# V04.net
KiCad netlist of a schematic drawn in Altium Designer
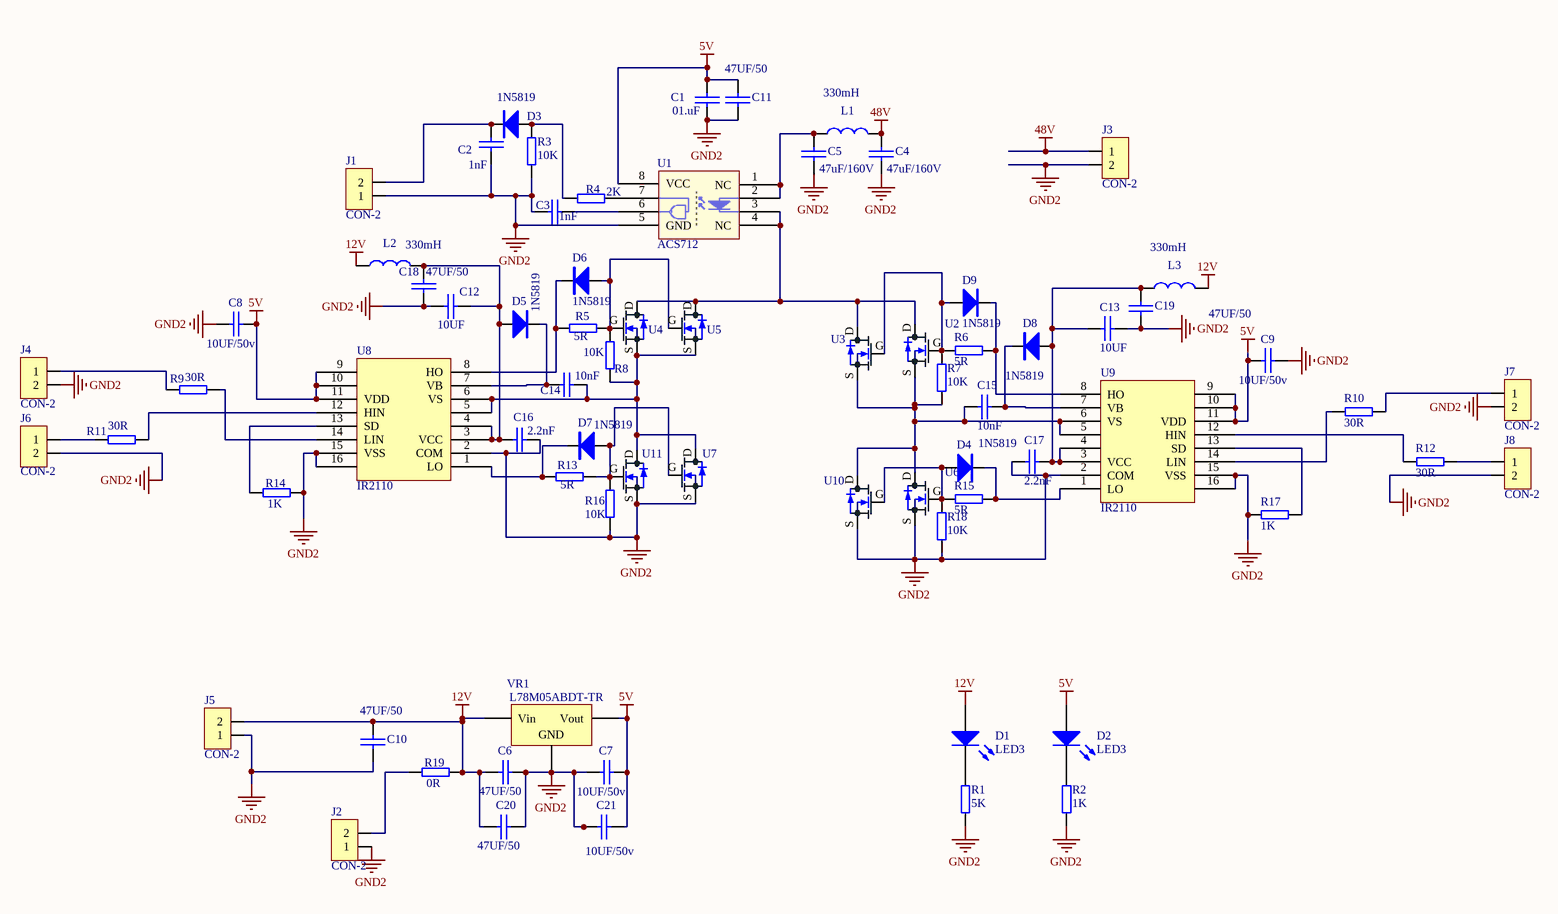
[diagram p0: 发送端V04.SchDoc]

(export (version "E")
  (design (tool "Eeschema 10.0.6"))
  (components
    (comp (ref "C1") (value "01.uF") (footprint "1206_C") (libsource (lib "WegeV1") (part "CAP")))
    (comp (ref "C2") (value "1nF") (footprint "1206_C") (libsource (lib "WegeV1") (part "CAP")))
    (comp (ref "C3") (value "1nF") (footprint "1206_C") (libsource (lib "WegeV1") (part "CAP")))
    (comp (ref "C4") (value "47uF/160V") (footprint "C3618") (libsource (lib "WegeV1") (part "CAP")))
    (comp (ref "C5") (value "47uF/160V") (footprint "C3618") (libsource (lib "WegeV1") (part "CAP")))
    (comp (ref "C6") (value "47UF/50") (footprint "1206_C") (libsource (lib "WegeV1") (part "CAP")))
    (comp (ref "C7") (value "10UF/50v") (footprint "1206_C") (libsource (lib "WegeV1") (part "CAP")))
    (comp (ref "C8") (value "10UF/50v") (footprint "1206_C") (libsource (lib "WegeV1") (part "CAP")))
    (comp (ref "C9") (value "10UF/50v") (footprint "1206_C") (libsource (lib "WegeV1") (part "CAP")))
    (comp (ref "C10") (value "47UF/50") (footprint "C1020") (libsource (lib "WegeV1") (part "CAP")))
    (comp (ref "C11") (value "47UF/50") (footprint "C1020") (libsource (lib "WegeV1") (part "CAP")))
    (comp (ref "C12") (value "10UF") (footprint "1206_C") (libsource (lib "WegeV1") (part "CAP")))
    (comp (ref "C13") (value "10UF") (footprint "1206_C") (libsource (lib "WegeV1") (part "CAP")))
    (comp (ref "C14") (value "10nF") (footprint "1206_C") (libsource (lib "WegeV1") (part "CAP")))
    (comp (ref "C15") (value "10nF") (footprint "1206_C") (libsource (lib "WegeV1") (part "CAP")))
    (comp (ref "C16") (value "2.2nF") (footprint "1206_C") (libsource (lib "WegeV1") (part "CAP")))
    (comp (ref "C17") (value "2.2nF") (footprint "1206_C") (libsource (lib "WegeV1") (part "CAP")))
    (comp (ref "C18") (value "47UF/50") (footprint "C1020") (libsource (lib "WegeV1") (part "CAP")))
    (comp (ref "C19") (value "47UF/50") (footprint "C1020") (libsource (lib "WegeV1") (part "CAP")))
    (comp (ref "C20") (value "47UF/50") (footprint "1206_C") (libsource (lib "WegeV1") (part "CAP")))
    (comp (ref "C21") (value "10UF/50v") (footprint "1206_C") (libsource (lib "WegeV1") (part "CAP")))
    (comp (ref "D1")
      (value "LED3")
      (footprint "1206_R")
      (description "Typical BLUE SiC LED")
      (fields (field (name "PUBLISHER") "Altium Limited"))
      (libsource (lib "Miscellaneous Devices") (part "LED3"))
    )
    (comp (ref "D2")
      (value "LED3")
      (footprint "1206_R")
      (description "Typical BLUE SiC LED")
      (fields (field (name "PUBLISHER") "Altium Limited"))
      (libsource (lib "Miscellaneous Devices") (part "LED3"))
    )
    (comp (ref "D3")
      (value "1N5819")
      (footprint "1206_R")
      (description "1N4148WS IN4148 0805 SOD323 丝印T4 贴片开关二极管")
      (libsource (lib "WegeV1") (part "1N4148"))
    )
    (comp (ref "D4")
      (value "1N5819")
      (footprint "1206_R")
      (description "1N4148WS IN4148 0805 SOD323 丝印T4 贴片开关二极管")
      (libsource (lib "WegeV1") (part "1N4148"))
    )
    (comp (ref "D5")
      (value "1N5819")
      (footprint "1206_R")
      (description "1N4148WS IN4148 0805 SOD323 丝印T4 贴片开关二极管")
      (libsource (lib "WegeV1") (part "1N4148"))
    )
    (comp (ref "D6")
      (value "1N5819")
      (footprint "1206_R")
      (description "1N4148WS IN4148 0805 SOD323 丝印T4 贴片开关二极管")
      (libsource (lib "WegeV1") (part "1N4148"))
    )
    (comp (ref "D7")
      (value "1N5819")
      (footprint "1206_R")
      (description "1N4148WS IN4148 0805 SOD323 丝印T4 贴片开关二极管")
      (libsource (lib "WegeV1") (part "1N4148"))
    )
    (comp (ref "D8")
      (value "1N5819")
      (footprint "1206_R")
      (description "1N4148WS IN4148 0805 SOD323 丝印T4 贴片开关二极管")
      (libsource (lib "WegeV1") (part "1N4148"))
    )
    (comp (ref "D9")
      (value "1N5819")
      (footprint "1206_R")
      (description "1N4148WS IN4148 0805 SOD323 丝印T4 贴片开关二极管")
      (libsource (lib "WegeV1") (part "1N4148"))
    )
    (comp (ref "J1") (value "CON-2") (footprint "HDR1X2") (libsource (lib "") (part "CON-2_1")))
    (comp (ref "J2") (value "CON-2") (footprint "HDR1X2") (libsource (lib "") (part "CON-2_1")))
    (comp (ref "J3") (value "CON-2") (footprint "F396P2-1") (libsource (lib "") (part "CON-2_2")))
    (comp (ref "J4") (value "CON-2") (footprint "GPSPIN") (libsource (lib "WegeV1") (part "CON-2")))
    (comp (ref "J5") (value "CON-2") (footprint "F396P2-1") (libsource (lib "") (part "CON-2_1")))
    (comp (ref "J6") (value "CON-2") (footprint "GPSPIN") (libsource (lib "WegeV1") (part "CON-2")))
    (comp (ref "J7") (value "CON-2") (footprint "GPSPIN") (libsource (lib "") (part "CON-2_2")))
    (comp (ref "J8") (value "CON-2") (footprint "GPSPIN") (libsource (lib "") (part "CON-2_2")))
    (comp (ref "L1")
      (value "330mH")
      (footprint "H3.3")
      (description "CD75--2.2mH 222M 贴片功率电感绕线功率电感 7*7.8*5mm")
      (libsource (lib "WegeV1") (part "INL"))
    )
    (comp (ref "L2")
      (value "330mH")
      (footprint "H3.3")
      (description "CD75--2.2mH 222M 贴片功率电感绕线功率电感 7*7.8*5mm")
      (libsource (lib "WegeV1") (part "INL"))
    )
    (comp (ref "L3")
      (value "330mH")
      (footprint "H3.3")
      (description "CD75--2.2mH 222M 贴片功率电感绕线功率电感 7*7.8*5mm")
      (libsource (lib "WegeV1") (part "INL"))
    )
    (comp (ref "R1") (value "5K") (footprint "1206_R") (libsource (lib "WegeV1") (part "RES")))
    (comp (ref "R2") (value "1K") (footprint "1206_R") (libsource (lib "WegeV1") (part "RES")))
    (comp (ref "R3") (value "10K") (footprint "1206_R") (libsource (lib "WegeV1") (part "RES")))
    (comp (ref "R4") (value "2K") (footprint "1206_R") (libsource (lib "WegeV1") (part "RES")))
    (comp (ref "R5") (value "5R") (footprint "1206_R") (libsource (lib "WegeV1") (part "RES")))
    (comp (ref "R6") (value "5R") (footprint "1206_R") (libsource (lib "WegeV1") (part "RES")))
    (comp (ref "R7") (value "10K") (footprint "1206_R") (libsource (lib "WegeV1") (part "RES")))
    (comp (ref "R8") (value "10K") (footprint "1206_R") (libsource (lib "WegeV1") (part "RES")))
    (comp (ref "R9") (value "30R") (footprint "1206_R") (libsource (lib "WegeV1") (part "RES")))
    (comp (ref "R10") (value "30R") (footprint "1206_R") (libsource (lib "WegeV1") (part "RES")))
    (comp (ref "R11") (value "30R") (footprint "1206_R") (libsource (lib "WegeV1") (part "RES")))
    (comp (ref "R12") (value "30R") (footprint "1206_R") (libsource (lib "WegeV1") (part "RES")))
    (comp (ref "R13") (value "5R") (footprint "1206_R") (libsource (lib "WegeV1") (part "RES")))
    (comp (ref "R14") (value "1K") (footprint "1206_R") (libsource (lib "WegeV1") (part "RES")))
    (comp (ref "R15") (value "5R") (footprint "1206_R") (libsource (lib "WegeV1") (part "RES")))
    (comp (ref "R16") (value "10K") (footprint "1206_R") (libsource (lib "WegeV1") (part "RES")))
    (comp (ref "R17") (value "1K") (footprint "1206_R") (libsource (lib "WegeV1") (part "RES")))
    (comp (ref "R18") (value "10K") (footprint "1206_R") (libsource (lib "WegeV1") (part "RES")))
    (comp (ref "R19") (value "0R") (footprint "1206_R") (libsource (lib "WegeV1") (part "RES")))
    (comp (ref "U1")
      (value "ACS712")
      (footprint "SOIC-8_150mil")
      (description "贴片光耦")
      (libsource (lib "Miscellaneous Devices LC") (part "6N137S(TA)_[C16496]"))
    )
    (comp (ref "U2") (value "IKW50N60H3") (footprint "TO-220") (libsource (lib "WegeV1") (part "NMOS")))
    (comp (ref "U3") (value "IKW50N60H3") (footprint "DDPak") (libsource (lib "WegeV1") (part "NMOS")))
    (comp (ref "U4") (value "IKW50N60H3") (footprint "TO-220") (libsource (lib "WegeV1") (part "NMOS")))
    (comp (ref "U5") (value "IKW50N60H3") (footprint "DDPak") (libsource (lib "WegeV1") (part "NMOS")))
    (comp (ref "U6") (value "IRFP4868") (footprint "TO-220") (libsource (lib "WegeV1") (part "NMOS")))
    (comp (ref "U7") (value "IRFP4868") (footprint "DDPak") (libsource (lib "WegeV1") (part "NMOS")))
    (comp (ref "U8")
      (value "IR2110")
      (footprint "SOIC-16_300mil")
      (libsource (lib "IC_temp") (part "IR2110"))
    )
    (comp (ref "U9") (value "IR2110") (footprint "SOIC-16_300mil") (libsource (lib "") (part "IR2110_1")))
    (comp (ref "U10") (value "IRFP4868") (footprint "DDPak") (libsource (lib "WegeV1") (part "NMOS")))
    (comp (ref "U11") (value "IRFP4868") (footprint "TO-220") (libsource (lib "WegeV1") (part "NMOS")))
    (comp (ref "VR1")
      (value "L78M05ABDT-TR")
      (footprint "TO-220")
      (description "低压差线性稳压(LDO)")
      (libsource (lib "Miscellaneous Devices LC") (part "TO-252-2 L78M05ABDT-TR"))
    )
  )
  (nets
    (net (code "1") (name "5V") (class "Default")
      (node (ref "C1") (pin "1") (pinfunction "1_1") (pintype "passive"))
      (node (ref "C11") (pin "1") (pinfunction "1_1") (pintype "passive"))
      (node (ref "C21") (pin "1") (pinfunction "1_1") (pintype "passive"))
      (node (ref "C7") (pin "1") (pinfunction "1_1") (pintype "passive"))
      (node (ref "C8") (pin "1") (pinfunction "1_1") (pintype "passive"))
      (node (ref "C9") (pin "2") (pinfunction "2_2") (pintype "passive"))
      (node (ref "D2") (pin "1") (pinfunction "A_1") (pintype "passive"))
      (node (ref "U1") (pin "8") (pinfunction "VCC_8") (pintype "passive"))
      (node (ref "U8") (pin "10") (pintype "passive"))
      (node (ref "U8") (pin "11") (pinfunction "VDD_11") (pintype "passive"))
      (node (ref "U8") (pin "9") (pintype "passive"))
      (node (ref "U9") (pin "10") (pintype "passive"))
      (node (ref "U9") (pin "11") (pinfunction "VDD_11") (pintype "passive"))
      (node (ref "U9") (pin "9") (pintype "passive"))
      (node (ref "VR1") (pin "S") (pinfunction "Vout_S") (pintype "passive"))
    )
    (net (code "2") (name "12V") (class "Default")
      (node (ref "C10") (pin "1") (pinfunction "1_1") (pintype "passive"))
      (node (ref "C20") (pin "2") (pinfunction "2_2") (pintype "passive"))
      (node (ref "C6") (pin "2") (pinfunction "2_2") (pintype "passive"))
      (node (ref "D1") (pin "1") (pinfunction "A_1") (pintype "passive"))
      (node (ref "J5") (pin "2") (pinfunction "2_2") (pintype "passive"))
      (node (ref "L2") (pin "2") (pinfunction "2_2") (pintype "passive"))
      (node (ref "L3") (pin "1") (pinfunction "1_1") (pintype "passive"))
      (node (ref "R19") (pin "2") (pinfunction "2_2") (pintype "passive"))
      (node (ref "VR1") (pin "G") (pinfunction "Vin_G") (pintype "passive"))
    )
    (net (code "3") (name "48V") (class "Default")
      (node (ref "C4") (pin "1") (pinfunction "1_1") (pintype "passive"))
      (node (ref "J3") (pin "1") (pinfunction "1_1") (pintype "passive"))
      (node (ref "L1") (pin "1") (pinfunction "1_1") (pintype "passive"))
    )
    (net (code "4") (name "GND2") (class "Default")
      (node (ref "C1") (pin "2") (pinfunction "2_2") (pintype "passive"))
      (node (ref "C10") (pin "2") (pinfunction "2_2") (pintype "passive"))
      (node (ref "C11") (pin "2") (pinfunction "2_2") (pintype "passive"))
      (node (ref "C12") (pin "2") (pinfunction "2_2") (pintype "passive"))
      (node (ref "C13") (pin "2") (pinfunction "2_2") (pintype "passive"))
      (node (ref "C16") (pin "1") (pinfunction "1_1") (pintype "passive"))
      (node (ref "C17") (pin "1") (pinfunction "1_1") (pintype "passive"))
      (node (ref "C18") (pin "2") (pinfunction "2_2") (pintype "passive"))
      (node (ref "C19") (pin "2") (pinfunction "2_2") (pintype "passive"))
      (node (ref "C2") (pin "2") (pinfunction "2_2") (pintype "passive"))
      (node (ref "C20") (pin "1") (pinfunction "1_1") (pintype "passive"))
      (node (ref "C21") (pin "2") (pinfunction "2_2") (pintype "passive"))
      (node (ref "C3") (pin "2") (pinfunction "2_2") (pintype "passive"))
      (node (ref "C4") (pin "2") (pinfunction "2_2") (pintype "passive"))
      (node (ref "C5") (pin "2") (pinfunction "2_2") (pintype "passive"))
      (node (ref "C6") (pin "1") (pinfunction "1_1") (pintype "passive"))
      (node (ref "C7") (pin "2") (pinfunction "2_2") (pintype "passive"))
      (node (ref "C8") (pin "2") (pinfunction "2_2") (pintype "passive"))
      (node (ref "C9") (pin "1") (pinfunction "1_1") (pintype "passive"))
      (node (ref "J1") (pin "1") (pinfunction "1_1") (pintype "passive"))
      (node (ref "J2") (pin "1") (pinfunction "1_1") (pintype "passive"))
      (node (ref "J3") (pin "2") (pinfunction "2_2") (pintype "passive"))
      (node (ref "J4") (pin "2") (pinfunction "2_2") (pintype "passive"))
      (node (ref "J5") (pin "1") (pinfunction "1_1") (pintype "passive"))
      (node (ref "J6") (pin "2") (pinfunction "2_2") (pintype "passive"))
      (node (ref "J7") (pin "2") (pinfunction "2_2") (pintype "passive"))
      (node (ref "J8") (pin "2") (pinfunction "2_2") (pintype "passive"))
      (node (ref "R1") (pin "1") (pinfunction "1_1") (pintype "passive"))
      (node (ref "R14") (pin "2") (pinfunction "2_2") (pintype "passive"))
      (node (ref "R16") (pin "1") (pinfunction "1_1") (pintype "passive"))
      (node (ref "R17") (pin "2") (pinfunction "2_2") (pintype "passive"))
      (node (ref "R18") (pin "1") (pinfunction "1_1") (pintype "passive"))
      (node (ref "R2") (pin "1") (pinfunction "1_1") (pintype "passive"))
      (node (ref "R3") (pin "2") (pinfunction "2_2") (pintype "passive"))
      (node (ref "U1") (pin "5") (pinfunction "GND_5") (pintype "passive"))
      (node (ref "U10") (pin "S") (pinfunction "S_S") (pintype "passive"))
      (node (ref "U11") (pin "S") (pinfunction "S_S") (pintype "passive"))
      (node (ref "U6") (pin "S") (pinfunction "S_S") (pintype "passive"))
      (node (ref "U7") (pin "S") (pinfunction "S_S") (pintype "passive"))
      (node (ref "U8") (pin "15") (pinfunction "VSS_15") (pintype "passive"))
      (node (ref "U8") (pin "16") (pintype "passive"))
      (node (ref "U8") (pin "2") (pinfunction "COM_2") (pintype "passive"))
      (node (ref "U9") (pin "15") (pinfunction "VSS_15") (pintype "passive"))
      (node (ref "U9") (pin "16") (pintype "passive"))
      (node (ref "U9") (pin "2") (pinfunction "COM_2") (pintype "passive"))
      (node (ref "VR1") (pin "D") (pinfunction "GND_D") (pintype "passive"))
    )
    (net (code "5") (name "Net-(D1-K)") (class "Default")
      (node (ref "D1") (pin "2") (pinfunction "K_2") (pintype "passive"))
      (node (ref "R1") (pin "2") (pinfunction "2_2") (pintype "passive"))
    )
    (net (code "6") (name "Net-(D2-K)") (class "Default")
      (node (ref "D2") (pin "2") (pinfunction "K_2") (pintype "passive"))
      (node (ref "R2") (pin "2") (pinfunction "2_2") (pintype "passive"))
    )
    (net (code "7") (name "Net-(D3-A)") (class "Default")
      (node (ref "D3") (pin "1") (pinfunction "A_1") (pintype "passive"))
      (node (ref "R3") (pin "1") (pinfunction "1_1") (pintype "passive"))
      (node (ref "R4") (pin "2") (pinfunction "2_2") (pintype "passive"))
    )
    (net (code "8") (name "Net-(D3-K)") (class "Default")
      (node (ref "C2") (pin "1") (pinfunction "1_1") (pintype "passive"))
      (node (ref "D3") (pin "2") (pinfunction "K_2") (pintype "passive"))
      (node (ref "J1") (pin "2") (pinfunction "2_2") (pintype "passive"))
    )
    (net (code "9") (name "Net-(D4-A)") (class "Default")
      (node (ref "D4") (pin "1") (pinfunction "A_1") (pintype "passive"))
      (node (ref "R15") (pin "2") (pinfunction "2_2") (pintype "passive"))
      (node (ref "R18") (pin "2") (pinfunction "2_2") (pintype "passive"))
      (node (ref "U10") (pin "G") (pinfunction "G_G") (pintype "passive"))
      (node (ref "U6") (pin "G") (pinfunction "G_G") (pintype "passive"))
    )
    (net (code "10") (name "Net-(D4-K)") (class "Default")
      (node (ref "D4") (pin "2") (pinfunction "K_2") (pintype "passive"))
      (node (ref "R15") (pin "1") (pinfunction "1_1") (pintype "passive"))
      (node (ref "U9") (pin "1") (pinfunction "LO_1") (pintype "passive"))
    )
    (net (code "11") (name "Net-(D5-A)") (class "Default")
      (node (ref "C12") (pin "1") (pinfunction "1_1") (pintype "passive"))
      (node (ref "C16") (pin "2") (pinfunction "2_2") (pintype "passive"))
      (node (ref "C18") (pin "1") (pinfunction "1_1") (pintype "passive"))
      (node (ref "D5") (pin "1") (pinfunction "A_1") (pintype "passive"))
      (node (ref "L2") (pin "1") (pinfunction "1_1") (pintype "passive"))
      (node (ref "U8") (pin "3") (pinfunction "VCC_3") (pintype "passive"))
      (node (ref "U8") (pin "4") (pintype "passive"))
    )
    (net (code "12") (name "Net-(D5-K)") (class "Default")
      (node (ref "C14") (pin "2") (pinfunction "2_2") (pintype "passive"))
      (node (ref "D5") (pin "2") (pinfunction "K_2") (pintype "passive"))
      (node (ref "U8") (pin "7") (pinfunction "VB_7") (pintype "passive"))
    )
    (net (code "13") (name "Net-(D6-A)") (class "Default")
      (node (ref "D6") (pin "1") (pinfunction "A_1") (pintype "passive"))
      (node (ref "R5") (pin "2") (pinfunction "2_2") (pintype "passive"))
      (node (ref "R8") (pin "2") (pinfunction "2_2") (pintype "passive"))
      (node (ref "U4") (pin "G") (pinfunction "G_G") (pintype "passive"))
      (node (ref "U5") (pin "G") (pinfunction "G_G") (pintype "passive"))
    )
    (net (code "14") (name "Net-(D6-K)") (class "Default")
      (node (ref "D6") (pin "2") (pinfunction "K_2") (pintype "passive"))
      (node (ref "R5") (pin "1") (pinfunction "1_1") (pintype "passive"))
      (node (ref "U8") (pin "8") (pinfunction "HO_8") (pintype "passive"))
    )
    (net (code "15") (name "Net-(D7-A)") (class "Default")
      (node (ref "D7") (pin "1") (pinfunction "A_1") (pintype "passive"))
      (node (ref "R13") (pin "2") (pinfunction "2_2") (pintype "passive"))
      (node (ref "R16") (pin "2") (pinfunction "2_2") (pintype "passive"))
      (node (ref "U11") (pin "G") (pinfunction "G_G") (pintype "passive"))
      (node (ref "U7") (pin "G") (pinfunction "G_G") (pintype "passive"))
    )
    (net (code "16") (name "Net-(D7-K)") (class "Default")
      (node (ref "D7") (pin "2") (pinfunction "K_2") (pintype "passive"))
      (node (ref "R13") (pin "1") (pinfunction "1_1") (pintype "passive"))
      (node (ref "U8") (pin "1") (pinfunction "LO_1") (pintype "passive"))
    )
    (net (code "17") (name "Net-(D8-A)") (class "Default")
      (node (ref "C13") (pin "1") (pinfunction "1_1") (pintype "passive"))
      (node (ref "C17") (pin "2") (pinfunction "2_2") (pintype "passive"))
      (node (ref "C19") (pin "1") (pinfunction "1_1") (pintype "passive"))
      (node (ref "D8") (pin "1") (pinfunction "A_1") (pintype "passive"))
      (node (ref "L3") (pin "2") (pinfunction "2_2") (pintype "passive"))
      (node (ref "U9") (pin "3") (pinfunction "VCC_3") (pintype "passive"))
      (node (ref "U9") (pin "4") (pintype "passive"))
    )
    (net (code "18") (name "Net-(D8-K)") (class "Default")
      (node (ref "C15") (pin "2") (pinfunction "2_2") (pintype "passive"))
      (node (ref "D8") (pin "2") (pinfunction "K_2") (pintype "passive"))
      (node (ref "U9") (pin "7") (pinfunction "VB_7") (pintype "passive"))
    )
    (net (code "19") (name "Net-(D9-A)") (class "Default")
      (node (ref "D9") (pin "1") (pinfunction "A_1") (pintype "passive"))
      (node (ref "R6") (pin "2") (pinfunction "2_2") (pintype "passive"))
      (node (ref "R7") (pin "2") (pinfunction "2_2") (pintype "passive"))
      (node (ref "U2") (pin "G") (pinfunction "G_G") (pintype "passive"))
      (node (ref "U3") (pin "G") (pinfunction "G_G") (pintype "passive"))
    )
    (net (code "20") (name "Net-(D9-K)") (class "Default")
      (node (ref "D9") (pin "2") (pinfunction "K_2") (pintype "passive"))
      (node (ref "R6") (pin "1") (pinfunction "1_1") (pintype "passive"))
      (node (ref "U9") (pin "8") (pinfunction "HO_8") (pintype "passive"))
    )
    (net (code "21") (name "Net-(J2-Pad2)") (class "Default")
      (node (ref "J2") (pin "2") (pinfunction "2_2") (pintype "passive"))
      (node (ref "R19") (pin "1") (pinfunction "1_1") (pintype "passive"))
    )
    (net (code "22") (name "Net-(J4-Pad1)") (class "Default")
      (node (ref "J4") (pin "1") (pinfunction "1_1") (pintype "passive"))
      (node (ref "R9") (pin "1") (pinfunction "1_1") (pintype "passive"))
    )
    (net (code "23") (name "Net-(J6-Pad1)") (class "Default")
      (node (ref "J6") (pin "1") (pinfunction "1_1") (pintype "passive"))
      (node (ref "R11") (pin "1") (pinfunction "1_1") (pintype "passive"))
    )
    (net (code "24") (name "Net-(J7-Pad1)") (class "Default")
      (node (ref "J7") (pin "1") (pinfunction "1_1") (pintype "passive"))
      (node (ref "R10") (pin "1") (pinfunction "1_1") (pintype "passive"))
    )
    (net (code "25") (name "Net-(J8-Pad1)") (class "Default")
      (node (ref "J8") (pin "1") (pinfunction "1_1") (pintype "passive"))
      (node (ref "R12") (pin "1") (pinfunction "1_1") (pintype "passive"))
    )
    (net (code "26") (name "Net-(U1-A)") (class "Default")
      (node (ref "C5") (pin "1") (pinfunction "1_1") (pintype "passive"))
      (node (ref "L1") (pin "2") (pinfunction "2_2") (pintype "passive"))
      (node (ref "U1") (pin "1") (pinfunction "NC_1") (pintype "passive"))
      (node (ref "U1") (pin "2") (pinfunction "A_2") (pintype "passive"))
    )
    (net (code "27") (name "Net-(U1-K)") (class "Default")
      (node (ref "U1") (pin "3") (pinfunction "K_3") (pintype "passive"))
      (node (ref "U1") (pin "4") (pinfunction "NC_4") (pintype "passive"))
      (node (ref "U2") (pin "D") (pinfunction "D_D") (pintype "passive"))
      (node (ref "U3") (pin "D") (pinfunction "D_D") (pintype "passive"))
      (node (ref "U4") (pin "D") (pinfunction "D_D") (pintype "passive"))
      (node (ref "U5") (pin "D") (pinfunction "D_D") (pintype "passive"))
    )
    (net (code "28") (name "Net-(U1-VE)") (class "Default")
      (node (ref "R4") (pin "1") (pinfunction "1_1") (pintype "passive"))
      (node (ref "U1") (pin "7") (pinfunction "VE_7") (pintype "passive"))
    )
    (net (code "29") (name "Net-(U1-VO)") (class "Default")
      (node (ref "C3") (pin "1") (pinfunction "1_1") (pintype "passive"))
      (node (ref "U1") (pin "6") (pinfunction "VO_6") (pintype "passive"))
    )
    (net (code "30") (name "Net-(U8-HIN)") (class "Default")
      (node (ref "R11") (pin "2") (pinfunction "2_2") (pintype "passive"))
      (node (ref "U8") (pin "12") (pinfunction "HIN_12") (pintype "passive"))
    )
    (net (code "31") (name "Net-(U8-LIN)") (class "Default")
      (node (ref "R9") (pin "2") (pinfunction "2_2") (pintype "passive"))
      (node (ref "U8") (pin "14") (pinfunction "LIN_14") (pintype "passive"))
    )
    (net (code "32") (name "Net-(U8-SD)") (class "Default")
      (node (ref "R14") (pin "1") (pinfunction "1_1") (pintype "passive"))
      (node (ref "U8") (pin "13") (pinfunction "SD_13") (pintype "passive"))
    )
    (net (code "33") (name "Net-(U8-VS)") (class "Default")
      (node (ref "C14") (pin "1") (pinfunction "1_1") (pintype "passive"))
      (node (ref "R8") (pin "1") (pinfunction "1_1") (pintype "passive"))
      (node (ref "U11") (pin "D") (pinfunction "D_D") (pintype "passive"))
      (node (ref "U4") (pin "S") (pinfunction "S_S") (pintype "passive"))
      (node (ref "U5") (pin "S") (pinfunction "S_S") (pintype "passive"))
      (node (ref "U7") (pin "D") (pinfunction "D_D") (pintype "passive"))
      (node (ref "U8") (pin "5") (pintype "passive"))
      (node (ref "U8") (pin "6") (pinfunction "VS_6") (pintype "passive"))
    )
    (net (code "34") (name "Net-(U9-HIN)") (class "Default")
      (node (ref "R12") (pin "2") (pinfunction "2_2") (pintype "passive"))
      (node (ref "U9") (pin "12") (pinfunction "HIN_12") (pintype "passive"))
    )
    (net (code "35") (name "Net-(U9-LIN)") (class "Default")
      (node (ref "R10") (pin "2") (pinfunction "2_2") (pintype "passive"))
      (node (ref "U9") (pin "14") (pinfunction "LIN_14") (pintype "passive"))
    )
    (net (code "36") (name "Net-(U9-SD)") (class "Default")
      (node (ref "R17") (pin "1") (pinfunction "1_1") (pintype "passive"))
      (node (ref "U9") (pin "13") (pinfunction "SD_13") (pintype "passive"))
    )
    (net (code "37") (name "Net-(U9-VS)") (class "Default")
      (node (ref "C15") (pin "1") (pinfunction "1_1") (pintype "passive"))
      (node (ref "R7") (pin "1") (pinfunction "1_1") (pintype "passive"))
      (node (ref "U10") (pin "D") (pinfunction "D_D") (pintype "passive"))
      (node (ref "U2") (pin "S") (pinfunction "S_S") (pintype "passive"))
      (node (ref "U3") (pin "S") (pinfunction "S_S") (pintype "passive"))
      (node (ref "U6") (pin "D") (pinfunction "D_D") (pintype "passive"))
      (node (ref "U9") (pin "5") (pintype "passive"))
      (node (ref "U9") (pin "6") (pinfunction "VS_6") (pintype "passive"))
    )
  )
)
